# Sheet1.net
KiCad netlist of a schematic drawn in Altium Designer
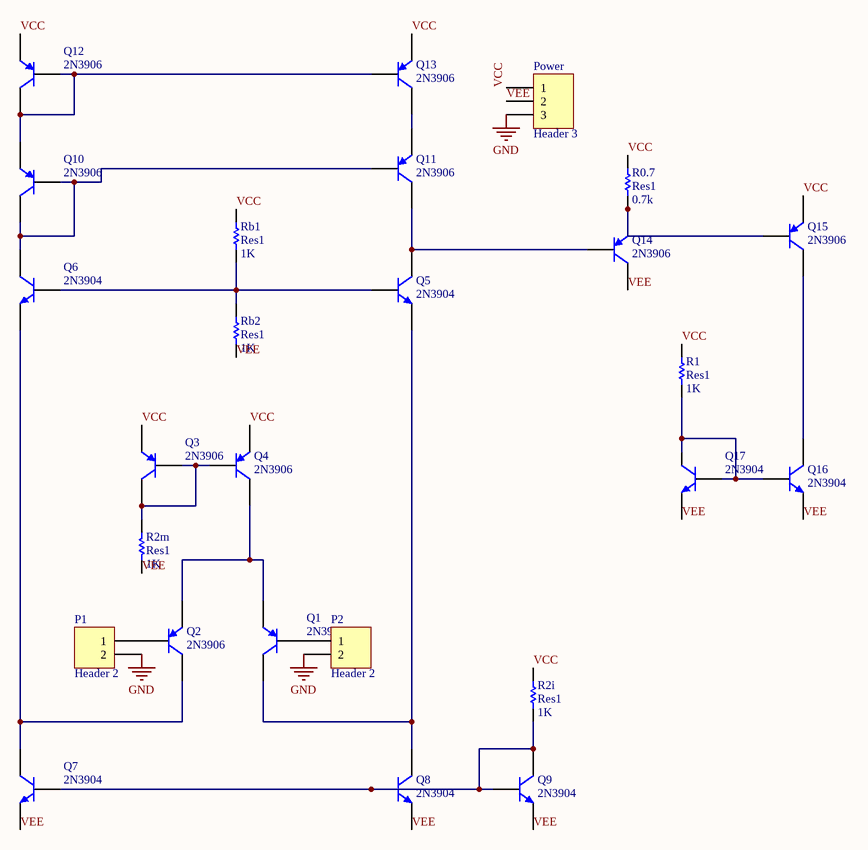
[diagram p0: Sheet1.SchDoc]

(export (version "E")
  (design (tool "Eeschema 10.0.6"))
  (components
    (comp (ref "P1")
      (value "Header 2")
      (footprint "HDR1X2")
      (description "Header, 2-Pin")
      (fields (field (name "PUBLISHER") "Altium Limited"))
      (libsource (lib "Miscellaneous Connectors") (part "Header 2"))
    )
    (comp (ref "P2")
      (value "Header 2")
      (footprint "HDR1X2")
      (description "Header, 2-Pin")
      (fields (field (name "PUBLISHER") "Altium Limited"))
      (libsource (lib "") (part "Header 2_1"))
    )
    (comp (ref "Power")
      (value "Header 3")
      (footprint "HDR1X3")
      (description "Header, 3-Pin")
      (fields (field (name "PUBLISHER") "Altium Limited"))
      (libsource (lib "Miscellaneous Connectors") (part "Header 3"))
    )
    (comp (ref "Q1")
      (value "2N3906")
      (footprint "TO-92A")
      (description "PNP General Purpose Amplifier")
      (fields (field (name "PUBLISHER") "Altium Limited"))
      (libsource (lib "Miscellaneous Devices") (part "2N3906"))
    )
    (comp (ref "Q2")
      (value "2N3906")
      (footprint "TO-92A")
      (description "PNP General Purpose Amplifier")
      (fields (field (name "PUBLISHER") "Altium Limited"))
      (libsource (lib "Miscellaneous Devices") (part "2N3906"))
    )
    (comp (ref "Q3")
      (value "2N3906")
      (footprint "TO-92A")
      (description "PNP General Purpose Amplifier")
      (fields (field (name "PUBLISHER") "Altium Limited"))
      (libsource (lib "Miscellaneous Devices") (part "2N3906"))
    )
    (comp (ref "Q4")
      (value "2N3906")
      (footprint "TO-92A")
      (description "PNP General Purpose Amplifier")
      (fields (field (name "PUBLISHER") "Altium Limited"))
      (libsource (lib "Miscellaneous Devices") (part "2N3906"))
    )
    (comp (ref "Q5")
      (value "2N3904")
      (footprint "TO-92A")
      (description "NPN General Purpose Amplifier")
      (fields (field (name "PUBLISHER") "Altium Limited"))
      (libsource (lib "Miscellaneous Devices") (part "2N3904"))
    )
    (comp (ref "Q6")
      (value "2N3904")
      (footprint "TO-92A")
      (description "NPN General Purpose Amplifier")
      (fields (field (name "PUBLISHER") "Altium Limited"))
      (libsource (lib "Miscellaneous Devices") (part "2N3904"))
    )
    (comp (ref "Q7")
      (value "2N3904")
      (footprint "TO-92A")
      (description "NPN General Purpose Amplifier")
      (fields (field (name "PUBLISHER") "Altium Limited"))
      (libsource (lib "Miscellaneous Devices") (part "2N3904"))
    )
    (comp (ref "Q8")
      (value "2N3904")
      (footprint "TO-92A")
      (description "NPN General Purpose Amplifier")
      (fields (field (name "PUBLISHER") "Altium Limited"))
      (libsource (lib "Miscellaneous Devices") (part "2N3904"))
    )
    (comp (ref "Q9")
      (value "2N3904")
      (footprint "TO-92A")
      (description "NPN General Purpose Amplifier")
      (fields (field (name "PUBLISHER") "Altium Limited"))
      (libsource (lib "Miscellaneous Devices") (part "2N3904"))
    )
    (comp (ref "Q10")
      (value "2N3906")
      (footprint "TO-92A")
      (description "PNP General Purpose Amplifier")
      (fields (field (name "PUBLISHER") "Altium Limited"))
      (libsource (lib "Miscellaneous Devices") (part "2N3906"))
    )
    (comp (ref "Q11")
      (value "2N3906")
      (footprint "TO-92A")
      (description "PNP General Purpose Amplifier")
      (fields (field (name "PUBLISHER") "Altium Limited"))
      (libsource (lib "Miscellaneous Devices") (part "2N3906"))
    )
    (comp (ref "Q12")
      (value "2N3906")
      (footprint "TO-92A")
      (description "PNP General Purpose Amplifier")
      (fields (field (name "PUBLISHER") "Altium Limited"))
      (libsource (lib "Miscellaneous Devices") (part "2N3906"))
    )
    (comp (ref "Q13")
      (value "2N3906")
      (footprint "TO-92A")
      (description "PNP General Purpose Amplifier")
      (fields (field (name "PUBLISHER") "Altium Limited"))
      (libsource (lib "Miscellaneous Devices") (part "2N3906"))
    )
    (comp (ref "Q14")
      (value "2N3906")
      (footprint "TO-92A")
      (description "PNP General Purpose Amplifier")
      (fields (field (name "PUBLISHER") "Altium Limited"))
      (libsource (lib "Miscellaneous Devices") (part "2N3906"))
    )
    (comp (ref "Q15")
      (value "2N3906")
      (footprint "TO-92A")
      (description "PNP General Purpose Amplifier")
      (fields (field (name "PUBLISHER") "Altium Limited"))
      (libsource (lib "Miscellaneous Devices") (part "2N3906"))
    )
    (comp (ref "Q16")
      (value "2N3904")
      (footprint "TO-92A")
      (description "NPN General Purpose Amplifier")
      (fields (field (name "PUBLISHER") "Altium Limited"))
      (libsource (lib "Miscellaneous Devices") (part "2N3904"))
    )
    (comp (ref "Q17")
      (value "2N3904")
      (footprint "TO-92A")
      (description "NPN General Purpose Amplifier")
      (fields (field (name "PUBLISHER") "Altium Limited"))
      (libsource (lib "Miscellaneous Devices") (part "2N3904"))
    )
    (comp (ref "R0.7")
      (value "Res1")
      (footprint "AXIAL-0.3")
      (description "Resistor")
      (fields (field (name "ALTIUM_VALUE") "0.7k") (field (name "PUBLISHER") "Altium Limited"))
      (libsource (lib "Miscellaneous Devices") (part "Res1"))
    )
    (comp (ref "R1")
      (value "Res1")
      (footprint "AXIAL-0.3")
      (description "Resistor")
      (fields (field (name "ALTIUM_VALUE") "1K") (field (name "PUBLISHER") "Altium Limited"))
      (libsource (lib "Miscellaneous Devices") (part "Res1"))
    )
    (comp (ref "R2i")
      (value "Res1")
      (footprint "AXIAL-0.3")
      (description "Resistor")
      (fields (field (name "ALTIUM_VALUE") "1K") (field (name "PUBLISHER") "Altium Limited"))
      (libsource (lib "Miscellaneous Devices") (part "Res1"))
    )
    (comp (ref "R2m")
      (value "Res1")
      (footprint "AXIAL-0.3")
      (description "Resistor")
      (fields (field (name "ALTIUM_VALUE") "1K") (field (name "PUBLISHER") "Altium Limited"))
      (libsource (lib "Miscellaneous Devices") (part "Res1"))
    )
    (comp (ref "Rb1")
      (value "Res1")
      (footprint "AXIAL-0.3")
      (description "Resistor")
      (fields (field (name "ALTIUM_VALUE") "1K") (field (name "PUBLISHER") "Altium Limited"))
      (libsource (lib "Miscellaneous Devices") (part "Res1"))
    )
    (comp (ref "Rb2")
      (value "Res1")
      (footprint "AXIAL-0.3")
      (description "Resistor")
      (fields (field (name "ALTIUM_VALUE") "1K") (field (name "PUBLISHER") "Altium Limited"))
      (libsource (lib "Miscellaneous Devices") (part "Res1"))
    )
  )
  (nets
    (net (code "1") (name "/VCC") (class "Default")
      (node (ref "Power") (pin "1") (pinfunction "1_1") (pintype "passive"))
      (node (ref "Q12") (pin "1") (pinfunction "E_1") (pintype "passive"))
      (node (ref "Q13") (pin "1") (pinfunction "E_1") (pintype "passive"))
      (node (ref "Q15") (pin "1") (pinfunction "E_1") (pintype "passive"))
      (node (ref "Q3") (pin "1") (pinfunction "E_1") (pintype "passive"))
      (node (ref "Q4") (pin "1") (pinfunction "E_1") (pintype "passive"))
      (node (ref "R0.7") (pin "2") (pinfunction "2_2") (pintype "passive"))
      (node (ref "R1") (pin "2") (pinfunction "2_2") (pintype "passive"))
      (node (ref "R2i") (pin "2") (pinfunction "2_2") (pintype "passive"))
      (node (ref "Rb1") (pin "2") (pinfunction "2_2") (pintype "passive"))
    )
    (net (code "2") (name "/VEE") (class "Default")
      (node (ref "Power") (pin "2") (pinfunction "2_2") (pintype "passive"))
      (node (ref "Q14") (pin "3") (pinfunction "C_3") (pintype "passive"))
      (node (ref "Q16") (pin "1") (pinfunction "E_1") (pintype "passive"))
      (node (ref "Q17") (pin "1") (pinfunction "E_1") (pintype "passive"))
      (node (ref "Q7") (pin "1") (pinfunction "E_1") (pintype "passive"))
      (node (ref "Q8") (pin "1") (pinfunction "E_1") (pintype "passive"))
      (node (ref "Q9") (pin "1") (pinfunction "E_1") (pintype "passive"))
      (node (ref "R2m") (pin "1") (pinfunction "1_1") (pintype "passive"))
      (node (ref "Rb2") (pin "1") (pinfunction "1_1") (pintype "passive"))
    )
    (net (code "3") (name "GND") (class "Default")
      (node (ref "P1") (pin "2") (pinfunction "2_2") (pintype "passive"))
      (node (ref "P2") (pin "2") (pinfunction "2_2") (pintype "passive"))
      (node (ref "Power") (pin "3") (pinfunction "3_3") (pintype "passive"))
    )
    (net (code "4") (name "Net-(Q1-B)") (class "Default")
      (node (ref "P2") (pin "1") (pinfunction "1_1") (pintype "passive"))
      (node (ref "Q1") (pin "2") (pinfunction "B_2") (pintype "passive"))
    )
    (net (code "5") (name "Net-(Q1-C)") (class "Default")
      (node (ref "Q1") (pin "3") (pinfunction "C_3") (pintype "passive"))
      (node (ref "Q5") (pin "1") (pinfunction "E_1") (pintype "passive"))
      (node (ref "Q8") (pin "3") (pinfunction "C_3") (pintype "passive"))
    )
    (net (code "6") (name "Net-(Q1-E)") (class "Default")
      (node (ref "Q1") (pin "1") (pinfunction "E_1") (pintype "passive"))
      (node (ref "Q2") (pin "1") (pinfunction "E_1") (pintype "passive"))
      (node (ref "Q4") (pin "3") (pinfunction "C_3") (pintype "passive"))
    )
    (net (code "7") (name "Net-(Q2-B)") (class "Default")
      (node (ref "P1") (pin "1") (pinfunction "1_1") (pintype "passive"))
      (node (ref "Q2") (pin "2") (pinfunction "B_2") (pintype "passive"))
    )
    (net (code "8") (name "Net-(Q2-C)") (class "Default")
      (node (ref "Q2") (pin "3") (pinfunction "C_3") (pintype "passive"))
      (node (ref "Q6") (pin "1") (pinfunction "E_1") (pintype "passive"))
      (node (ref "Q7") (pin "3") (pinfunction "C_3") (pintype "passive"))
    )
    (net (code "9") (name "Net-(Q3-B)") (class "Default")
      (node (ref "Q3") (pin "2") (pinfunction "B_2") (pintype "passive"))
      (node (ref "Q3") (pin "3") (pinfunction "C_3") (pintype "passive"))
      (node (ref "Q4") (pin "2") (pinfunction "B_2") (pintype "passive"))
      (node (ref "R2m") (pin "2") (pinfunction "2_2") (pintype "passive"))
    )
    (net (code "10") (name "Net-(Q5-B)") (class "Default")
      (node (ref "Q5") (pin "2") (pinfunction "B_2") (pintype "passive"))
      (node (ref "Q6") (pin "2") (pinfunction "B_2") (pintype "passive"))
      (node (ref "Rb1") (pin "1") (pinfunction "1_1") (pintype "passive"))
      (node (ref "Rb2") (pin "2") (pinfunction "2_2") (pintype "passive"))
    )
    (net (code "11") (name "Net-(Q7-B)") (class "Default")
      (node (ref "Q7") (pin "2") (pinfunction "B_2") (pintype "passive"))
      (node (ref "Q8") (pin "2") (pinfunction "B_2") (pintype "passive"))
      (node (ref "Q9") (pin "2") (pinfunction "B_2") (pintype "passive"))
      (node (ref "Q9") (pin "3") (pinfunction "C_3") (pintype "passive"))
      (node (ref "R2i") (pin "1") (pinfunction "1_1") (pintype "passive"))
    )
    (net (code "12") (name "Net-(Q10-B)") (class "Default")
      (node (ref "Q10") (pin "2") (pinfunction "B_2") (pintype "passive"))
      (node (ref "Q10") (pin "3") (pinfunction "C_3") (pintype "passive"))
      (node (ref "Q11") (pin "2") (pinfunction "B_2") (pintype "passive"))
      (node (ref "Q6") (pin "3") (pinfunction "C_3") (pintype "passive"))
    )
    (net (code "13") (name "Net-(Q10-E)") (class "Default")
      (node (ref "Q10") (pin "1") (pinfunction "E_1") (pintype "passive"))
      (node (ref "Q12") (pin "2") (pinfunction "B_2") (pintype "passive"))
      (node (ref "Q12") (pin "3") (pinfunction "C_3") (pintype "passive"))
      (node (ref "Q13") (pin "2") (pinfunction "B_2") (pintype "passive"))
    )
    (net (code "14") (name "Net-(Q11-C)") (class "Default")
      (node (ref "Q11") (pin "3") (pinfunction "C_3") (pintype "passive"))
      (node (ref "Q14") (pin "2") (pinfunction "B_2") (pintype "passive"))
      (node (ref "Q5") (pin "3") (pinfunction "C_3") (pintype "passive"))
    )
    (net (code "15") (name "Net-(Q11-E)") (class "Default")
      (node (ref "Q11") (pin "1") (pinfunction "E_1") (pintype "passive"))
      (node (ref "Q13") (pin "3") (pinfunction "C_3") (pintype "passive"))
    )
    (net (code "16") (name "Net-(Q14-E)") (class "Default")
      (node (ref "Q14") (pin "1") (pinfunction "E_1") (pintype "passive"))
      (node (ref "Q15") (pin "2") (pinfunction "B_2") (pintype "passive"))
      (node (ref "R0.7") (pin "1") (pinfunction "1_1") (pintype "passive"))
    )
    (net (code "17") (name "Net-(Q15-C)") (class "Default")
      (node (ref "Q15") (pin "3") (pinfunction "C_3") (pintype "passive"))
      (node (ref "Q16") (pin "3") (pinfunction "C_3") (pintype "passive"))
    )
    (net (code "18") (name "Net-(Q16-B)") (class "Default")
      (node (ref "Q16") (pin "2") (pinfunction "B_2") (pintype "passive"))
      (node (ref "Q17") (pin "2") (pinfunction "B_2") (pintype "passive"))
      (node (ref "Q17") (pin "3") (pinfunction "C_3") (pintype "passive"))
      (node (ref "R1") (pin "1") (pinfunction "1_1") (pintype "passive"))
    )
  )
)
